# comms_sys_schematic_V1.net
KiCad netlist of a schematic drawn in EAGLE
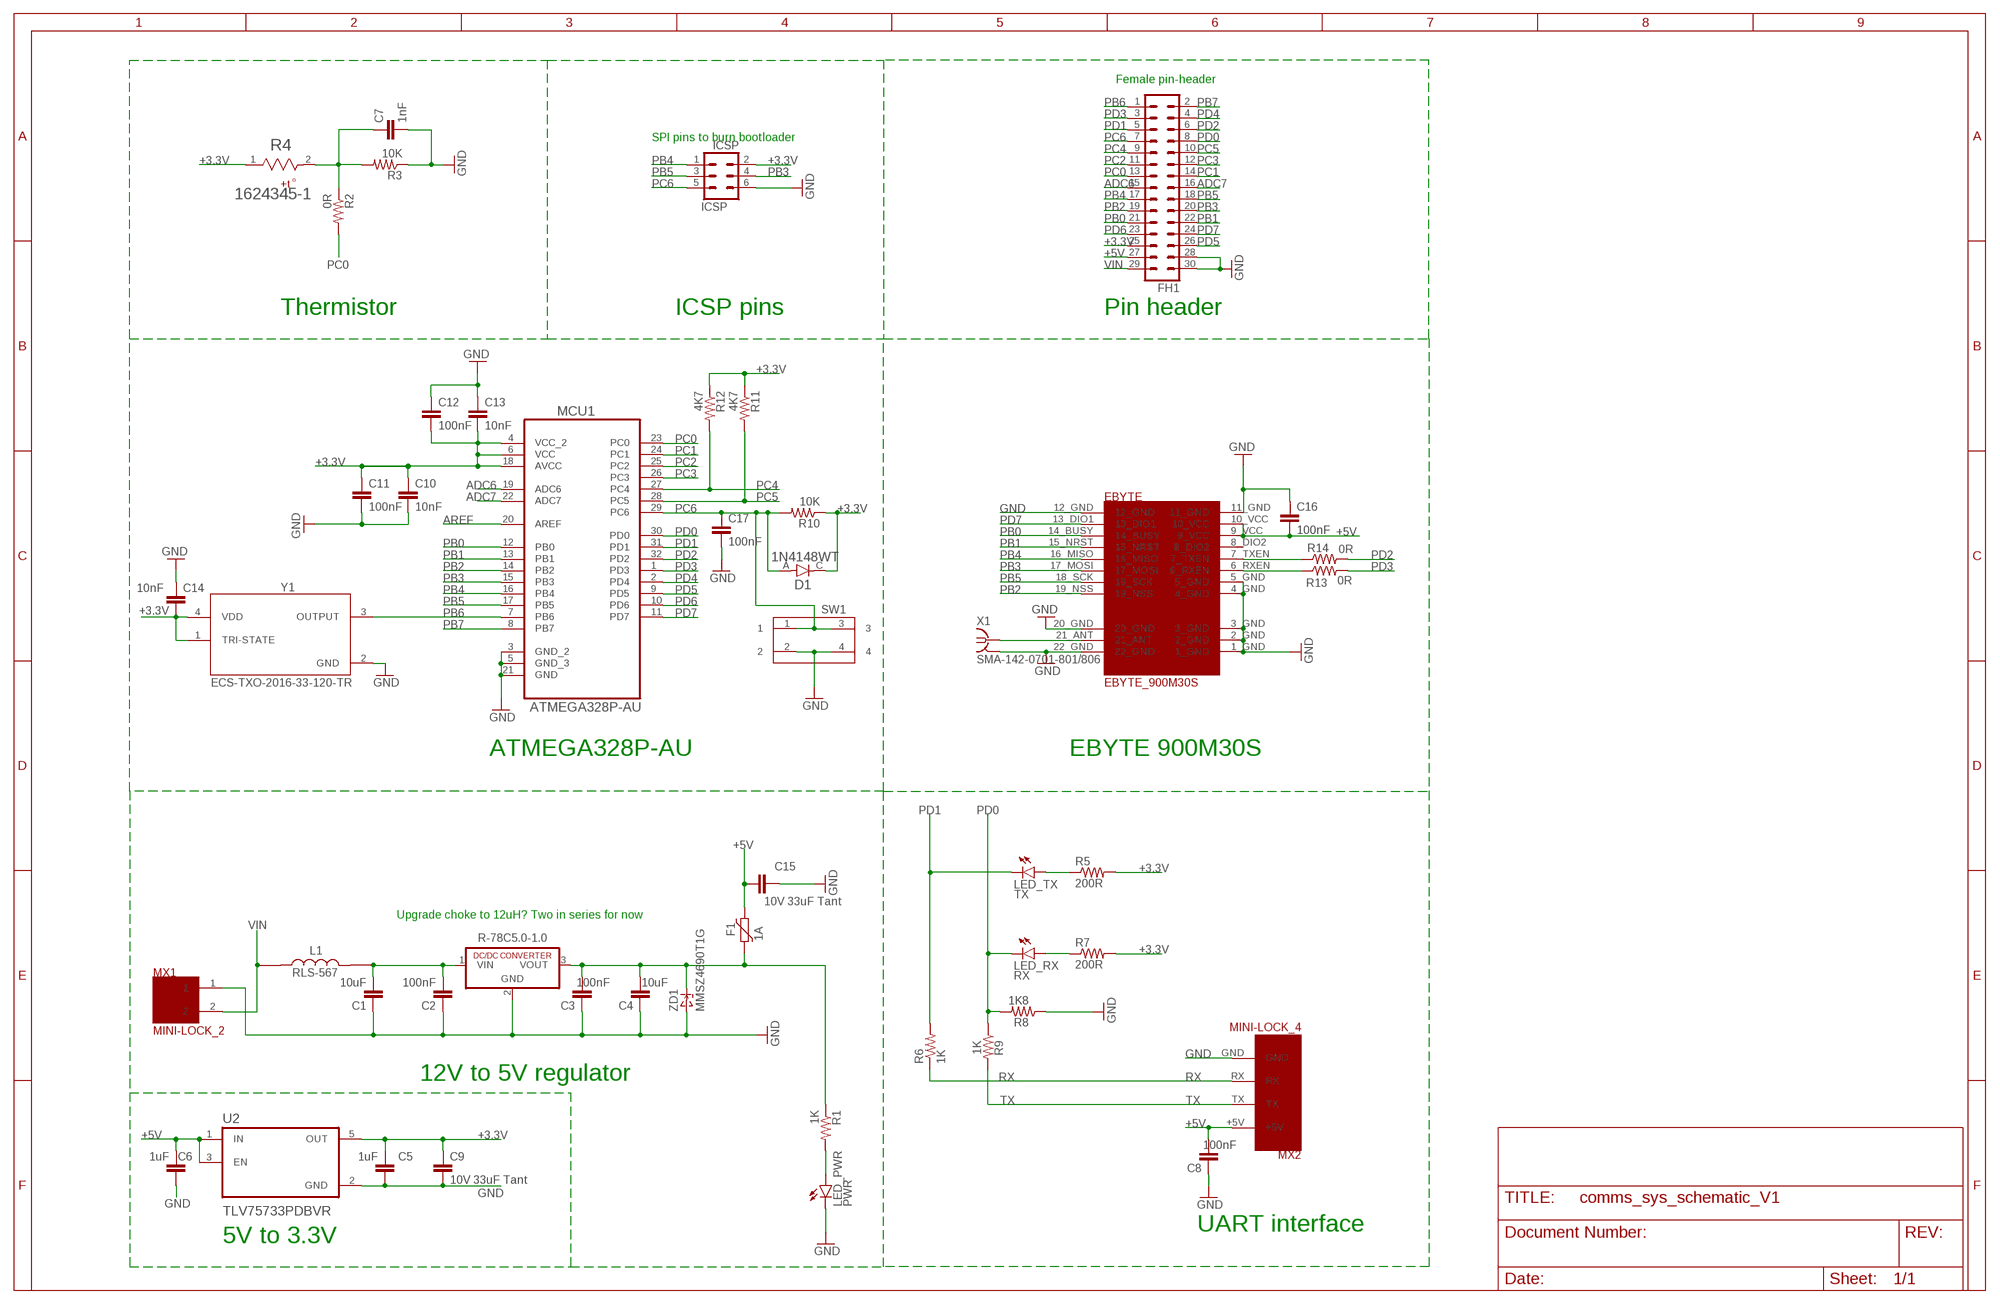
[diagram p0: schematic, sheet 1]

(export (version "E")
  (design (tool "Eeschema 10.0.6"))
  (components
    (comp (ref "C1")
      (value "10uF")
      (footprint "eagle-import:C0805")
      (libsource (lib "eagle-import") (part "C-EUC0805"))
    )
    (comp (ref "C2")
      (value "100nF")
      (footprint "eagle-import:C0805")
      (libsource (lib "eagle-import") (part "C-EUC0805"))
    )
    (comp (ref "C3")
      (value "100nF")
      (footprint "eagle-import:C0805")
      (libsource (lib "eagle-import") (part "C-EUC0805"))
    )
    (comp (ref "C4")
      (value "10uF")
      (footprint "eagle-import:C0805")
      (libsource (lib "eagle-import") (part "C-EUC0805"))
    )
    (comp (ref "C5")
      (value "1uF")
      (footprint "eagle-import:C0805")
      (libsource (lib "eagle-import") (part "C-EUC0805"))
    )
    (comp (ref "C6")
      (value "1uF")
      (footprint "eagle-import:C0805")
      (libsource (lib "eagle-import") (part "C-EUC0805"))
    )
    (comp (ref "C7")
      (value "1nF")
      (footprint "eagle-import:C0805")
      (libsource (lib "eagle-import") (part "C-EUC0805"))
    )
    (comp (ref "C8")
      (value "100nF")
      (footprint "eagle-import:C0805")
      (libsource (lib "eagle-import") (part "C-EUC0805"))
    )
    (comp (ref "C9")
      (value "10V 33uF Tant")
      (footprint "eagle-import:C1206")
      (libsource (lib "eagle-import") (part "C-EUC1206"))
    )
    (comp (ref "C10")
      (value "10nF")
      (footprint "eagle-import:C0805")
      (libsource (lib "eagle-import") (part "C-EUC0805"))
    )
    (comp (ref "C11")
      (value "100nF")
      (footprint "eagle-import:C0805")
      (libsource (lib "eagle-import") (part "C-EUC0805"))
    )
    (comp (ref "C12")
      (value "100nF")
      (footprint "eagle-import:C0805")
      (libsource (lib "eagle-import") (part "C-EUC0805"))
    )
    (comp (ref "C13")
      (value "10nF")
      (footprint "eagle-import:C0805")
      (libsource (lib "eagle-import") (part "C-EUC0805"))
    )
    (comp (ref "C14")
      (value "10nF")
      (footprint "eagle-import:C0805")
      (libsource (lib "eagle-import") (part "C-EUC0805"))
    )
    (comp (ref "C15")
      (value "10V 33uF Tant")
      (footprint "eagle-import:C1206")
      (libsource (lib "eagle-import") (part "C-EUC1206"))
    )
    (comp (ref "C16")
      (value "100nF")
      (footprint "eagle-import:C0805")
      (libsource (lib "eagle-import") (part "C-EUC0805"))
    )
    (comp (ref "C17")
      (value "100nF")
      (footprint "eagle-import:C0805")
      (libsource (lib "eagle-import") (part "C-EUC0805"))
    )
    (comp (ref "D1")
      (value "1N4148WT")
      (footprint "eagle-import:SODFL1608X70N")
      (fields (field (name "DIGI-KEY_PART_NUMBER") "1N4148WTCT-ND") (field (name "MF") "ON Semiconductor"))
      (libsource (lib "eagle-import") (part "1N4148WT"))
    )
    (comp (ref "EBYTE")
      (value "EBYTE_900M30S")
      (footprint "eagle-import:EBYTE_SX1262_900M30S_FOOTPRINT")
      (libsource (lib "eagle-import") (part "EBYTE_SX1262_900M30S"))
    )
    (comp (ref "F1")
      (value "1A")
      (footprint "eagle-import:PTC0805")
      (libsource (lib "eagle-import") (part "FUSE_PTC-0805"))
    )
    (comp (ref "FH1")
      (value "MA15-2")
      (footprint "eagle-import:MA15-2")
      (libsource (lib "eagle-import") (part "MA15-2"))
    )
    (comp (ref "ICSP")
      (value "ICSP")
      (footprint "eagle-import:MA03-2")
      (libsource (lib "eagle-import") (part "MA03-2"))
    )
    (comp (ref "L1")
      (value "RLS-567")
      (footprint "eagle-import:IND_RLS-567")
      (fields (field (name "MF") "Recom Power"))
      (libsource (lib "eagle-import") (part "RLS-567"))
    )
    (comp (ref "LED_PWR")
      (value "PWR")
      (footprint "eagle-import:CHIP-LED0805")
      (libsource (lib "eagle-import") (part "LEDCHIP-LED0805"))
    )
    (comp (ref "LED_RX")
      (value "RX")
      (footprint "eagle-import:CHIP-LED0805")
      (libsource (lib "eagle-import") (part "LEDCHIP-LED0805"))
    )
    (comp (ref "LED_TX")
      (value "TX")
      (footprint "eagle-import:CHIP-LED0805")
      (libsource (lib "eagle-import") (part "LEDCHIP-LED0805"))
    )
    (comp (ref "MCU1")
      (value "ATMEGA328P-AU")
      (footprint "eagle-import:QFP80P900X900X120-32N")
      (libsource (lib "eagle-import") (part "ATMEGA328P-AU"))
    )
    (comp (ref "MX1")
      (value "MINI-LOCK_2")
      (footprint "eagle-import:MINI-LOCK_2")
      (libsource (lib "eagle-import") (part "MINI-LOCK_2"))
    )
    (comp (ref "MX2")
      (value "MINI-LOCK_4")
      (footprint "eagle-import:MINI-LOCK_4")
      (libsource (lib "eagle-import") (part "MINI-LOCK_4"))
    )
    (comp (ref "R1")
      (value "1K")
      (footprint "eagle-import:R0805")
      (libsource (lib "eagle-import") (part "R-US_R0805"))
    )
    (comp (ref "R2")
      (value "0R")
      (footprint "eagle-import:R0805")
      (libsource (lib "eagle-import") (part "R-US_R0805"))
    )
    (comp (ref "R3")
      (value "10K")
      (footprint "eagle-import:R0805")
      (libsource (lib "eagle-import") (part "R-US_R0805"))
    )
    (comp (ref "R4")
      (value "1624345-1")
      (footprint "eagle-import:THRMC2012X50N")
      (fields
        (field (name "DIGI-KEY_PART_NUMBER") "A106104CT-ND")
        (field (name "MF") "TE Connectivity")
        (field (name "MP") "NTC0805J10K")
      )
      (libsource (lib "eagle-import") (part "1624345-1"))
    )
    (comp (ref "R5")
      (value "200R")
      (footprint "eagle-import:R0805")
      (libsource (lib "eagle-import") (part "R-US_R0805"))
    )
    (comp (ref "R6")
      (value "1K")
      (footprint "eagle-import:R0805")
      (libsource (lib "eagle-import") (part "R-US_R0805"))
    )
    (comp (ref "R7")
      (value "200R")
      (footprint "eagle-import:R0805")
      (libsource (lib "eagle-import") (part "R-US_R0805"))
    )
    (comp (ref "R8")
      (value "1K8")
      (footprint "eagle-import:R0805")
      (libsource (lib "eagle-import") (part "R-US_R0805"))
    )
    (comp (ref "R9")
      (value "1K")
      (footprint "eagle-import:R0805")
      (libsource (lib "eagle-import") (part "R-US_R0805"))
    )
    (comp (ref "R10")
      (value "10K")
      (footprint "eagle-import:R0805")
      (libsource (lib "eagle-import") (part "R-US_R0805"))
    )
    (comp (ref "R11")
      (value "4K7")
      (footprint "eagle-import:R0805")
      (libsource (lib "eagle-import") (part "R-US_R0805"))
    )
    (comp (ref "R12")
      (value "4K7")
      (footprint "eagle-import:R0805")
      (libsource (lib "eagle-import") (part "R-US_R0805"))
    )
    (comp (ref "R13")
      (value "0R")
      (footprint "eagle-import:R0805")
      (libsource (lib "eagle-import") (part "R-US_R0805"))
    )
    (comp (ref "R14")
      (value "0R")
      (footprint "eagle-import:R0805")
      (libsource (lib "eagle-import") (part "R-US_R0805"))
    )
    (comp (ref "SW1")
      (value "430152043826")
      (footprint "eagle-import:430152043826")
      (libsource (lib "eagle-import") (part "430152043826"))
    )
    (comp (ref "U1")
      (value "R-78C5.0-1.0")
      (footprint "eagle-import:SIP3")
      (libsource (lib "eagle-import") (part "R-78C-1.05.0"))
    )
    (comp (ref "U2")
      (value "TLV75733PDBVR")
      (footprint "eagle-import:SOT95P280X145-5N")
      (fields (field (name "DIGI-KEY_PART_NUMBER") "296-50414-1-ND") (field (name "MF") "Texas Instruments"))
      (libsource (lib "eagle-import") (part "TLV75733PDBVR"))
    )
    (comp (ref "X1")
      (value "SMA-142-0701-801/806")
      (footprint "eagle-import:J502-ND-142-0701-801_806")
      (fields (field (name "MF") "JOHNSON COMPONENTS") (field (name "MPN") "142-0701-801"))
      (libsource (lib "eagle-import") (part "SMA-142-0701-801/806"))
    )
    (comp (ref "Y1")
      (value "ECS-TXO-2016-33-120-TR")
      (footprint "eagle-import:OSC_ECS-TXO-2016-33-120-TR")
      (fields (field (name "DIGI-KEY_PART_NUMBER") "XC3160CT-ND") (field (name "MF") "ECS Inc."))
      (libsource (lib "eagle-import") (part "ECS-TXO-2016-33-120-TR"))
    )
    (comp (ref "ZD1")
      (value "MMSZ4690T1G")
      (footprint "eagle-import:SOD-123")
      (libsource (lib "eagle-import") (part "ZENERSOD-123"))
    )
  )
  (nets
    (net (code "1") (name "/+3.3V") (class "Default")
      (node (ref "C10") (pin "1") (pinfunction "1_1") (pintype "passive"))
      (node (ref "C11") (pin "1") (pinfunction "1_1") (pintype "passive"))
      (node (ref "C12") (pin "2") (pinfunction "2_2") (pintype "passive"))
      (node (ref "C13") (pin "2") (pinfunction "2_2") (pintype "passive"))
      (node (ref "C14") (pin "2") (pinfunction "2_2") (pintype "passive"))
      (node (ref "C5") (pin "2") (pinfunction "2_2") (pintype "passive"))
      (node (ref "C9") (pin "1") (pinfunction "1_1") (pintype "passive"))
      (node (ref "D1") (pin "C") (pinfunction "C_C") (pintype "passive"))
      (node (ref "FH1") (pin "25") (pinfunction "29_25") (pintype "passive"))
      (node (ref "ICSP") (pin "2") (pinfunction "2_2") (pintype "passive"))
      (node (ref "MCU1") (pin "18") (pinfunction "AVCC_18") (pintype "power_in"))
      (node (ref "MCU1") (pin "4") (pinfunction "VCC_2_4") (pintype "power_in"))
      (node (ref "MCU1") (pin "6") (pinfunction "VCC_6") (pintype "power_in"))
      (node (ref "R10") (pin "1") (pinfunction "1_1") (pintype "passive"))
      (node (ref "R11") (pin "1") (pinfunction "1_1") (pintype "passive"))
      (node (ref "R12") (pin "1") (pinfunction "1_1") (pintype "passive"))
      (node (ref "R4") (pin "1") (pinfunction "1_1") (pintype "passive"))
      (node (ref "R5") (pin "2") (pinfunction "2_2") (pintype "passive"))
      (node (ref "R7") (pin "2") (pinfunction "2_2") (pintype "passive"))
      (node (ref "U2") (pin "5") (pinfunction "OUT_5") (pintype "output"))
      (node (ref "Y1") (pin "1") (pinfunction "TRI-STATE_1") (pintype "input"))
      (node (ref "Y1") (pin "4") (pinfunction "VDD_4") (pintype "input"))
    )
    (net (code "2") (name "/+5V") (class "Default")
      (node (ref "C15") (pin "1") (pinfunction "1_1") (pintype "passive"))
      (node (ref "C16") (pin "2") (pinfunction "2_2") (pintype "passive"))
      (node (ref "C6") (pin "2") (pinfunction "2_2") (pintype "passive"))
      (node (ref "C8") (pin "2") (pinfunction "2_2") (pintype "passive"))
      (node (ref "EBYTE") (pin "10_VCC") (pinfunction "10_VCC_10_VCC") (pintype "power_in"))
      (node (ref "EBYTE") (pin "9_VCC") (pinfunction "9_VCC_9_VCC") (pintype "power_in"))
      (node (ref "F1") (pin "2") (pinfunction "2_2") (pintype "passive"))
      (node (ref "FH1") (pin "27") (pinfunction "31_27") (pintype "passive"))
      (node (ref "MX2") (pin "+5V") (pinfunction "+5V_+5V") (pintype "bidirectional"))
      (node (ref "U2") (pin "1") (pinfunction "IN_1") (pintype "input"))
      (node (ref "U2") (pin "3") (pinfunction "EN_3") (pintype "bidirectional"))
    )
    (net (code "3") (name "/ADC6") (class "Default")
      (node (ref "FH1") (pin "15") (pinfunction "19_15") (pintype "passive"))
      (node (ref "MCU1") (pin "19") (pinfunction "ADC6_19") (pintype "input"))
    )
    (net (code "4") (name "/ADC7") (class "Default")
      (node (ref "FH1") (pin "16") (pinfunction "20_16") (pintype "passive"))
      (node (ref "MCU1") (pin "22") (pinfunction "ADC7_22") (pintype "input"))
    )
    (net (code "5") (name "/AREF") (class "Default")
      (node (ref "MCU1") (pin "20") (pinfunction "AREF_20") (pintype "input"))
    )
    (net (code "6") (name "/PB0") (class "Default")
      (node (ref "EBYTE") (pin "14_BUSY") (pinfunction "14_BUSY_14_BUSY") (pintype "bidirectional"))
      (node (ref "FH1") (pin "21") (pinfunction "25_21") (pintype "passive"))
      (node (ref "MCU1") (pin "12") (pinfunction "PB0_12") (pintype "bidirectional"))
    )
    (net (code "7") (name "/PB1") (class "Default")
      (node (ref "EBYTE") (pin "15_NRST") (pinfunction "15_NRST_15_NRST") (pintype "bidirectional"))
      (node (ref "FH1") (pin "22") (pinfunction "26_22") (pintype "passive"))
      (node (ref "MCU1") (pin "13") (pinfunction "PB1_13") (pintype "bidirectional"))
    )
    (net (code "8") (name "/PB2") (class "Default")
      (node (ref "EBYTE") (pin "19_NSS") (pinfunction "19_NSS_19_NSS") (pintype "bidirectional"))
      (node (ref "FH1") (pin "19") (pinfunction "23_19") (pintype "passive"))
      (node (ref "MCU1") (pin "14") (pinfunction "PB2_14") (pintype "bidirectional"))
    )
    (net (code "9") (name "/PB3") (class "Default")
      (node (ref "EBYTE") (pin "17_MOSI") (pinfunction "17_MOSI_17_MOSI") (pintype "bidirectional"))
      (node (ref "FH1") (pin "20") (pinfunction "24_20") (pintype "passive"))
      (node (ref "ICSP") (pin "4") (pinfunction "4_4") (pintype "passive"))
      (node (ref "MCU1") (pin "15") (pinfunction "PB3_15") (pintype "bidirectional"))
    )
    (net (code "10") (name "/PB4") (class "Default")
      (node (ref "EBYTE") (pin "16_MISO") (pinfunction "16_MISO_16_MISO") (pintype "bidirectional"))
      (node (ref "FH1") (pin "17") (pinfunction "21_17") (pintype "passive"))
      (node (ref "ICSP") (pin "1") (pinfunction "1_1") (pintype "passive"))
      (node (ref "MCU1") (pin "16") (pinfunction "PB4_16") (pintype "bidirectional"))
    )
    (net (code "11") (name "/PB5") (class "Default")
      (node (ref "EBYTE") (pin "18_SCK") (pinfunction "18_SCK_18_SCK") (pintype "bidirectional"))
      (node (ref "FH1") (pin "18") (pinfunction "22_18") (pintype "passive"))
      (node (ref "ICSP") (pin "3") (pinfunction "3_3") (pintype "passive"))
      (node (ref "MCU1") (pin "17") (pinfunction "PB5_17") (pintype "bidirectional"))
    )
    (net (code "12") (name "/PB6") (class "Default")
      (node (ref "FH1") (pin "1") (pinfunction "5_1") (pintype "passive"))
      (node (ref "MCU1") (pin "7") (pinfunction "PB6_7") (pintype "bidirectional"))
      (node (ref "Y1") (pin "3") (pinfunction "OUTPUT_3") (pintype "output"))
    )
    (net (code "13") (name "/PB7") (class "Default")
      (node (ref "FH1") (pin "2") (pinfunction "6_2") (pintype "passive"))
      (node (ref "MCU1") (pin "8") (pinfunction "PB7_8") (pintype "bidirectional"))
    )
    (net (code "14") (name "/PC0") (class "Default")
      (node (ref "FH1") (pin "13") (pinfunction "17_13") (pintype "passive"))
      (node (ref "MCU1") (pin "23") (pinfunction "PC0_23") (pintype "bidirectional"))
      (node (ref "R2") (pin "2") (pinfunction "2_2") (pintype "passive"))
    )
    (net (code "15") (name "/PC1") (class "Default")
      (node (ref "FH1") (pin "14") (pinfunction "18_14") (pintype "passive"))
      (node (ref "MCU1") (pin "24") (pinfunction "PC1_24") (pintype "bidirectional"))
    )
    (net (code "16") (name "/PC2") (class "Default")
      (node (ref "FH1") (pin "11") (pinfunction "15_11") (pintype "passive"))
      (node (ref "MCU1") (pin "25") (pinfunction "PC2_25") (pintype "bidirectional"))
    )
    (net (code "17") (name "/PC3") (class "Default")
      (node (ref "FH1") (pin "12") (pinfunction "16_12") (pintype "passive"))
      (node (ref "MCU1") (pin "26") (pinfunction "PC3_26") (pintype "bidirectional"))
    )
    (net (code "18") (name "/PC4") (class "Default")
      (node (ref "FH1") (pin "9") (pinfunction "13_9") (pintype "passive"))
      (node (ref "MCU1") (pin "27") (pinfunction "PC4_27") (pintype "bidirectional"))
      (node (ref "R12") (pin "2") (pinfunction "2_2") (pintype "passive"))
    )
    (net (code "19") (name "/PC5") (class "Default")
      (node (ref "FH1") (pin "10") (pinfunction "14_10") (pintype "passive"))
      (node (ref "MCU1") (pin "28") (pinfunction "PC5_28") (pintype "bidirectional"))
      (node (ref "R11") (pin "2") (pinfunction "2_2") (pintype "passive"))
    )
    (net (code "20") (name "/PC6") (class "Default")
      (node (ref "C17") (pin "1") (pinfunction "1_1") (pintype "passive"))
      (node (ref "D1") (pin "A") (pinfunction "A_A") (pintype "passive"))
      (node (ref "FH1") (pin "7") (pinfunction "11_7") (pintype "passive"))
      (node (ref "ICSP") (pin "5") (pinfunction "5_5") (pintype "passive"))
      (node (ref "MCU1") (pin "29") (pinfunction "PC6_29") (pintype "bidirectional"))
      (node (ref "R10") (pin "2") (pinfunction "2_2") (pintype "passive"))
      (node (ref "SW1") (pin "1") (pinfunction "1_1") (pintype "bidirectional"))
      (node (ref "SW1") (pin "3") (pinfunction "3_3") (pintype "bidirectional"))
    )
    (net (code "21") (name "/PD0") (class "Default")
      (node (ref "FH1") (pin "8") (pinfunction "12_8") (pintype "passive"))
      (node (ref "LED_RX") (pin "C") (pinfunction "C_C") (pintype "passive"))
      (node (ref "MCU1") (pin "30") (pinfunction "PD0_30") (pintype "bidirectional"))
      (node (ref "R8") (pin "2") (pinfunction "2_2") (pintype "passive"))
      (node (ref "R9") (pin "1") (pinfunction "1_1") (pintype "passive"))
    )
    (net (code "22") (name "/PD1") (class "Default")
      (node (ref "FH1") (pin "5") (pinfunction "9_5") (pintype "passive"))
      (node (ref "LED_TX") (pin "C") (pinfunction "C_C") (pintype "passive"))
      (node (ref "MCU1") (pin "31") (pinfunction "PD1_31") (pintype "bidirectional"))
      (node (ref "R6") (pin "2") (pinfunction "2_2") (pintype "passive"))
    )
    (net (code "23") (name "/PD2") (class "Default")
      (node (ref "FH1") (pin "6") (pinfunction "10_6") (pintype "passive"))
      (node (ref "MCU1") (pin "32") (pinfunction "PD2_32") (pintype "bidirectional"))
      (node (ref "R14") (pin "2") (pinfunction "2_2") (pintype "passive"))
    )
    (net (code "24") (name "/PD3") (class "Default")
      (node (ref "FH1") (pin "3") (pinfunction "7_3") (pintype "passive"))
      (node (ref "MCU1") (pin "1") (pinfunction "PD3_1") (pintype "bidirectional"))
      (node (ref "R13") (pin "2") (pinfunction "2_2") (pintype "passive"))
    )
    (net (code "25") (name "/PD4") (class "Default")
      (node (ref "FH1") (pin "4") (pinfunction "8_4") (pintype "passive"))
      (node (ref "MCU1") (pin "2") (pinfunction "PD4_2") (pintype "bidirectional"))
    )
    (net (code "26") (name "/PD5") (class "Default")
      (node (ref "FH1") (pin "26") (pinfunction "30_26") (pintype "passive"))
      (node (ref "MCU1") (pin "9") (pinfunction "PD5_9") (pintype "bidirectional"))
    )
    (net (code "27") (name "/PD6") (class "Default")
      (node (ref "FH1") (pin "23") (pinfunction "27_23") (pintype "passive"))
      (node (ref "MCU1") (pin "10") (pinfunction "PD6_10") (pintype "bidirectional"))
    )
    (net (code "28") (name "/PD7") (class "Default")
      (node (ref "EBYTE") (pin "13_DIO1") (pinfunction "13_DIO1_13_DIO1") (pintype "bidirectional"))
      (node (ref "FH1") (pin "24") (pinfunction "28_24") (pintype "passive"))
      (node (ref "MCU1") (pin "11") (pinfunction "PD7_11") (pintype "bidirectional"))
    )
    (net (code "29") (name "/RX") (class "Default")
      (node (ref "MX2") (pin "RX") (pinfunction "RX_RX") (pintype "bidirectional"))
      (node (ref "R6") (pin "1") (pinfunction "1_1") (pintype "passive"))
    )
    (net (code "30") (name "/TX") (class "Default")
      (node (ref "MX2") (pin "TX") (pinfunction "TX_TX") (pintype "bidirectional"))
      (node (ref "R9") (pin "2") (pinfunction "2_2") (pintype "passive"))
    )
    (net (code "31") (name "/VIN") (class "Default")
      (node (ref "FH1") (pin "29") (pinfunction "33_29") (pintype "passive"))
      (node (ref "L1") (pin "1") (pinfunction "1_1") (pintype "passive"))
      (node (ref "MX1") (pin "2") (pinfunction "2_2") (pintype "bidirectional"))
    )
    (net (code "32") (name "GND") (class "Default")
      (node (ref "C1") (pin "1") (pinfunction "1_1") (pintype "passive"))
      (node (ref "C10") (pin "2") (pinfunction "2_2") (pintype "passive"))
      (node (ref "C11") (pin "2") (pinfunction "2_2") (pintype "passive"))
      (node (ref "C12") (pin "1") (pinfunction "1_1") (pintype "passive"))
      (node (ref "C13") (pin "1") (pinfunction "1_1") (pintype "passive"))
      (node (ref "C14") (pin "1") (pinfunction "1_1") (pintype "passive"))
      (node (ref "C15") (pin "2") (pinfunction "2_2") (pintype "passive"))
      (node (ref "C16") (pin "1") (pinfunction "1_1") (pintype "passive"))
      (node (ref "C17") (pin "2") (pinfunction "2_2") (pintype "passive"))
      (node (ref "C2") (pin "1") (pinfunction "1_1") (pintype "passive"))
      (node (ref "C3") (pin "1") (pinfunction "1_1") (pintype "passive"))
      (node (ref "C4") (pin "1") (pinfunction "1_1") (pintype "passive"))
      (node (ref "C5") (pin "1") (pinfunction "1_1") (pintype "passive"))
      (node (ref "C6") (pin "1") (pinfunction "1_1") (pintype "passive"))
      (node (ref "C7") (pin "2") (pinfunction "2_2") (pintype "passive"))
      (node (ref "C8") (pin "1") (pinfunction "1_1") (pintype "passive"))
      (node (ref "C9") (pin "2") (pinfunction "2_2") (pintype "passive"))
      (node (ref "EBYTE") (pin "11_GND") (pinfunction "11_GND_11_GND") (pintype "power_in"))
      (node (ref "EBYTE") (pin "12_GND") (pinfunction "12_GND_12_GND") (pintype "power_in"))
      (node (ref "EBYTE") (pin "1_GND") (pinfunction "1_GND_1_GND") (pintype "power_in"))
      (node (ref "EBYTE") (pin "20_GND") (pinfunction "20_GND_20_GND") (pintype "power_in"))
      (node (ref "EBYTE") (pin "22_GND") (pinfunction "22_GND_22_GND") (pintype "power_in"))
      (node (ref "EBYTE") (pin "2_GND") (pinfunction "2_GND_2_GND") (pintype "power_in"))
      (node (ref "EBYTE") (pin "3_GND") (pinfunction "3_GND_3_GND") (pintype "power_in"))
      (node (ref "EBYTE") (pin "4_GND") (pinfunction "4_GND_4_GND") (pintype "power_in"))
      (node (ref "EBYTE") (pin "5_GND") (pinfunction "5_GND_5_GND") (pintype "power_in"))
      (node (ref "FH1") (pin "28") (pinfunction "32_28") (pintype "passive"))
      (node (ref "FH1") (pin "30") (pinfunction "34_30") (pintype "passive"))
      (node (ref "ICSP") (pin "6") (pinfunction "6_6") (pintype "passive"))
      (node (ref "LED_PWR") (pin "C") (pinfunction "C_C") (pintype "passive"))
      (node (ref "MCU1") (pin "21") (pinfunction "GND_21") (pintype "passive"))
      (node (ref "MCU1") (pin "3") (pinfunction "GND_2_3") (pintype "passive"))
      (node (ref "MCU1") (pin "5") (pinfunction "GND_3_5") (pintype "passive"))
      (node (ref "MX1") (pin "1") (pinfunction "1_1") (pintype "bidirectional"))
      (node (ref "MX2") (pin "GND") (pinfunction "GND_GND") (pintype "bidirectional"))
      (node (ref "R3") (pin "1") (pinfunction "1_1") (pintype "passive"))
      (node (ref "R8") (pin "1") (pinfunction "1_1") (pintype "passive"))
      (node (ref "SW1") (pin "2") (pinfunction "2_2") (pintype "bidirectional"))
      (node (ref "SW1") (pin "4") (pinfunction "4_4") (pintype "bidirectional"))
      (node (ref "U1") (pin "2") (pinfunction "GND_2") (pintype "passive"))
      (node (ref "U2") (pin "2") (pinfunction "GND_2") (pintype "power_in"))
      (node (ref "X1") (pin "G@1") (pinfunction "2_G@1") (pintype "passive"))
      (node (ref "X1") (pin "G@2") (pinfunction "2_G@2") (pintype "passive"))
      (node (ref "X1") (pin "G@3") (pinfunction "2_G@3") (pintype "passive"))
      (node (ref "X1") (pin "G@4") (pinfunction "2_G@4") (pintype "passive"))
      (node (ref "Y1") (pin "2") (pinfunction "GND_2") (pintype "power_in"))
      (node (ref "ZD1") (pin "A") (pinfunction "A_A") (pintype "passive"))
    )
    (net (code "33") (name "Net-(C7-Pad1)") (class "Default")
      (node (ref "C7") (pin "1") (pinfunction "1_1") (pintype "passive"))
      (node (ref "R2") (pin "1") (pinfunction "1_1") (pintype "passive"))
      (node (ref "R3") (pin "2") (pinfunction "2_2") (pintype "passive"))
      (node (ref "R4") (pin "2") (pinfunction "2_2") (pintype "passive"))
    )
    (net (code "34") (name "Net-(EBYTE-Pad6_RXEN)") (class "Default")
      (node (ref "EBYTE") (pin "6_RXEN") (pinfunction "6_RXEN_6_RXEN") (pintype "bidirectional"))
      (node (ref "R13") (pin "1") (pinfunction "1_1") (pintype "passive"))
    )
    (net (code "35") (name "Net-(EBYTE-Pad7_TXEN)") (class "Default")
      (node (ref "EBYTE") (pin "7_TXEN") (pinfunction "7_TXEN_7_TXEN") (pintype "bidirectional"))
      (node (ref "R14") (pin "1") (pinfunction "1_1") (pintype "passive"))
    )
    (net (code "36") (name "Net-(EBYTE-Pad21_ANT)") (class "Default")
      (node (ref "EBYTE") (pin "21_ANT") (pinfunction "21_ANT_21_ANT") (pintype "bidirectional"))
      (node (ref "X1") (pin "1") (pinfunction "1_1") (pintype "passive"))
    )
    (net (code "37") (name "Net-(LED_PWR-PadA)") (class "Default")
      (node (ref "LED_PWR") (pin "A") (pinfunction "A_A") (pintype "passive"))
      (node (ref "R1") (pin "2") (pinfunction "2_2") (pintype "passive"))
    )
    (net (code "38") (name "Net-(LED_RX-PadA)") (class "Default")
      (node (ref "LED_RX") (pin "A") (pinfunction "A_A") (pintype "passive"))
      (node (ref "R7") (pin "1") (pinfunction "1_1") (pintype "passive"))
    )
    (net (code "39") (name "Net-(LED_TX-PadA)") (class "Default")
      (node (ref "LED_TX") (pin "A") (pinfunction "A_A") (pintype "passive"))
      (node (ref "R5") (pin "1") (pinfunction "1_1") (pintype "passive"))
    )
    (net (code "40") (name "Net-(U1-VIN)") (class "Default")
      (node (ref "C1") (pin "2") (pinfunction "2_2") (pintype "passive"))
      (node (ref "C2") (pin "2") (pinfunction "2_2") (pintype "passive"))
      (node (ref "L1") (pin "2") (pinfunction "2_2") (pintype "passive"))
      (node (ref "U1") (pin "1") (pinfunction "VIN_1") (pintype "passive"))
    )
    (net (code "41") (name "Net-(U1-VOUT)") (class "Default")
      (node (ref "C3") (pin "2") (pinfunction "2_2") (pintype "passive"))
      (node (ref "C4") (pin "2") (pinfunction "2_2") (pintype "passive"))
      (node (ref "F1") (pin "1") (pinfunction "1_1") (pintype "passive"))
      (node (ref "R1") (pin "1") (pinfunction "1_1") (pintype "passive"))
      (node (ref "U1") (pin "3") (pinfunction "VOUT_3") (pintype "passive"))
      (node (ref "ZD1") (pin "C") (pinfunction "C_C") (pintype "passive"))
    )
    (net (code "42") (name "unconnected-(EBYTE-Pad8_DIO2)") (class "Default")
      (node (ref "EBYTE") (pin "8_DIO2") (pinfunction "8_DIO2_8_DIO2") (pintype "bidirectional"))
    )
  )
)
